# PCB-ENCODERSOLO.net
KiCad netlist of a schematic drawn in EAGLE
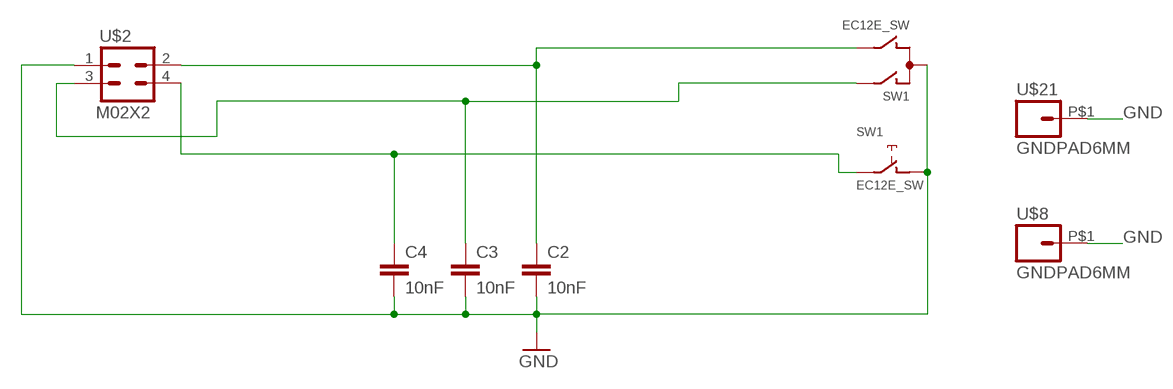
[diagram p0: schematic, sheet 1]

(export (version "E")
  (design (tool "Eeschema 10.0.6"))
  (components
    (comp (ref "C2")
      (value "10nF")
      (footprint "eagle-import:0603-CAP")
      (libsource (lib "eagle-import") (part "CAP0603-CAP"))
    )
    (comp (ref "C3")
      (value "10nF")
      (footprint "eagle-import:0603-CAP")
      (libsource (lib "eagle-import") (part "CAP0603-CAP"))
    )
    (comp (ref "C4")
      (value "10nF")
      (footprint "eagle-import:0603-CAP")
      (libsource (lib "eagle-import") (part "CAP0603-CAP"))
    )
    (comp (ref "SW1")
      (value "EC12E_SW")
      (footprint "eagle-import:ALPS_EC12E_SW")
      (fields (field (name "MPN") "EC12E2424407"))
      (libsource (lib "eagle-import") (part "EC12E_SW"))
    )
    (comp (ref "U$2")
      (value "M02X2")
      (footprint "eagle-import:2X2")
      (libsource (lib "eagle-import") (part "M02X2"))
    )
    (comp (ref "U$8")
      (value "GNDPAD6MM")
      (footprint "eagle-import:3.2MMPAD6MM")
      (libsource (lib "eagle-import") (part "GNDPAD6MM"))
    )
    (comp (ref "U$21")
      (value "GNDPAD6MM")
      (footprint "eagle-import:3.2MMPAD6MM")
      (libsource (lib "eagle-import") (part "GNDPAD6MM"))
    )
  )
  (nets
    (net (code "1") (name "GND") (class "Default")
      (node (ref "C2") (pin "2") (pinfunction "2_2") (pintype "passive"))
      (node (ref "C3") (pin "2") (pinfunction "2_2") (pintype "passive"))
      (node (ref "C4") (pin "2") (pinfunction "2_2") (pintype "passive"))
      (node (ref "SW1") (pin "C") (pinfunction "C_C") (pintype "passive"))
      (node (ref "SW1") (pin "D") (pinfunction "1_D") (pintype "passive"))
      (node (ref "U$2") (pin "1") (pinfunction "1_1") (pintype "passive"))
      (node (ref "U$21") (pin "P$1") (pinfunction "1_P$1") (pintype "passive"))
      (node (ref "U$8") (pin "P$1") (pinfunction "1_P$1") (pintype "passive"))
    )
    (net (code "2") (name "Net-(C2-Pad1)") (class "Default")
      (node (ref "C2") (pin "1") (pinfunction "1_1") (pintype "passive"))
      (node (ref "SW1") (pin "B") (pinfunction "B_B") (pintype "passive"))
      (node (ref "U$2") (pin "2") (pinfunction "2_2") (pintype "passive"))
    )
    (net (code "3") (name "Net-(C3-Pad1)") (class "Default")
      (node (ref "C3") (pin "1") (pinfunction "1_1") (pintype "passive"))
      (node (ref "SW1") (pin "A") (pinfunction "A_A") (pintype "passive"))
      (node (ref "U$2") (pin "3") (pinfunction "3_3") (pintype "passive"))
    )
    (net (code "4") (name "Net-(SW1B-2)") (class "Default")
      (node (ref "C4") (pin "1") (pinfunction "1_1") (pintype "passive"))
      (node (ref "SW1") (pin "E") (pinfunction "2_E") (pintype "passive"))
      (node (ref "U$2") (pin "4") (pinfunction "4_4") (pintype "passive"))
    )
  )
)
